# RADIO.net
KiCad netlist of a schematic drawn in Altium Designer
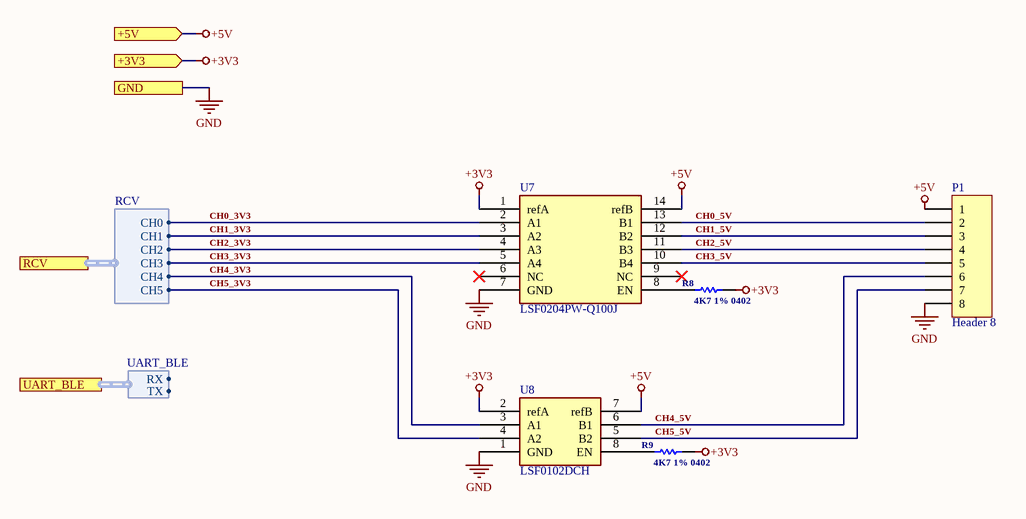
[diagram p0: RADIO.SchDoc]

(export (version "E")
  (design (tool "Eeschema 10.0.6"))
  (components
    (comp (ref "P1")
      (value "Header 8")
      (footprint "HDR1X8")
      (description "Header, 8-Pin")
      (fields (field (name "PUBLISHER") "Altium Limited"))
      (libsource (lib "Miscellaneous Connectors") (part "Header 8"))
    )
    (comp (ref "R8")
      (value "4K7 1% 0402")
      (footprint "Resistor_0402")
      (description "Thick Film Resistors 1/16W 4.7K ohm 1% AEC-Q200")
      (fields
        (field (name "MANUFACTURER") "Yageo")
        (field (name "MANUFACTURER PART NUMBER") "AC0402FR-074K7L")
      )
      (libsource (lib "ResistenciasGenericas") (part "AC0402FR-074K7L 4.7K 1% 0402"))
    )
    (comp (ref "R9")
      (value "4K7 1% 0402")
      (footprint "Resistor_0402")
      (description "Thick Film Resistors 1/16W 4.7K ohm 1% AEC-Q200")
      (fields
        (field (name "MANUFACTURER") "Yageo")
        (field (name "MANUFACTURER PART NUMBER") "AC0402FR-074K7L")
      )
      (libsource (lib "ResistenciasGenericas") (part "AC0402FR-074K7L 4.7K 1% 0402"))
    )
    (comp (ref "U7")
      (value "LSF0204PW-Q100J")
      (footprint "TSOP65P640X110-14N")
      (description "Nivel de voltaje Traductores Bidireccional 1 circuitos 4 canales 120MHz 14-TSSOP")
      (libsource (lib "LevelConversors") (part "LSF0204PW-Q100J"))
    )
    (comp (ref "U8")
      (value "LSF0102DCH")
      (description "Voltage Level Translator Bidirectional 1 Circuit 2 Channel 100MHz 8-VSSOP")
      (libsource (lib "LevelConversors") (part "LSF0102DCH"))
    )
  )
  (nets
    (net (code "3") (name "+3V3") (class "Default")
      (node (ref "R8") (pin "2") (pinfunction "2_2") (pintype "passive"))
      (node (ref "R9") (pin "2") (pinfunction "2_2") (pintype "passive"))
      (node (ref "U7") (pin "1") (pinfunction "refA_1") (pintype "passive"))
      (node (ref "U8") (pin "2") (pinfunction "refA_2") (pintype "passive"))
    )
    (net (code "4") (name "+5V") (class "Default")
      (node (ref "P1") (pin "1") (pinfunction "1_1") (pintype "passive"))
      (node (ref "U7") (pin "14") (pinfunction "refB_14") (pintype "passive"))
      (node (ref "U8") (pin "7") (pinfunction "refB_7") (pintype "passive"))
    )
    (net (code "5") (name "/CH0_3V3") (class "Default")
      (node (ref "U7") (pin "2") (pinfunction "A1_2") (pintype "passive"))
    )
    (net (code "6") (name "/CH0_5V") (class "Default")
      (node (ref "P1") (pin "2") (pinfunction "2_2") (pintype "passive"))
      (node (ref "U7") (pin "13") (pinfunction "B1_13") (pintype "passive"))
    )
    (net (code "7") (name "/CH1_3V3") (class "Default")
      (node (ref "U7") (pin "3") (pinfunction "A2_3") (pintype "passive"))
    )
    (net (code "8") (name "/CH1_5V") (class "Default")
      (node (ref "P1") (pin "3") (pinfunction "3_3") (pintype "passive"))
      (node (ref "U7") (pin "12") (pinfunction "B2_12") (pintype "passive"))
    )
    (net (code "9") (name "/CH2_3V3") (class "Default")
      (node (ref "U7") (pin "4") (pinfunction "A3_4") (pintype "passive"))
    )
    (net (code "10") (name "/CH2_5V") (class "Default")
      (node (ref "P1") (pin "4") (pinfunction "4_4") (pintype "passive"))
      (node (ref "U7") (pin "11") (pinfunction "B3_11") (pintype "passive"))
    )
    (net (code "11") (name "/CH3_3V3") (class "Default")
      (node (ref "U7") (pin "5") (pinfunction "A4_5") (pintype "passive"))
    )
    (net (code "12") (name "/CH3_5V") (class "Default")
      (node (ref "P1") (pin "5") (pinfunction "5_5") (pintype "passive"))
      (node (ref "U7") (pin "10") (pinfunction "B4_10") (pintype "passive"))
    )
    (net (code "13") (name "/CH4_3V3") (class "Default")
      (node (ref "U8") (pin "3") (pinfunction "A1_3") (pintype "passive"))
    )
    (net (code "14") (name "/CH4_5V") (class "Default")
      (node (ref "P1") (pin "6") (pinfunction "6_6") (pintype "passive"))
      (node (ref "U8") (pin "6") (pinfunction "B1_6") (pintype "passive"))
    )
    (net (code "15") (name "/CH5_3V3") (class "Default")
      (node (ref "U8") (pin "4") (pinfunction "A2_4") (pintype "passive"))
    )
    (net (code "16") (name "/CH5_5V") (class "Default")
      (node (ref "P1") (pin "7") (pinfunction "7_7") (pintype "passive"))
      (node (ref "U8") (pin "5") (pinfunction "B2_5") (pintype "passive"))
    )
    (net (code "19") (name "GND") (class "Default")
      (node (ref "P1") (pin "8") (pinfunction "8_8") (pintype "passive"))
      (node (ref "U7") (pin "7") (pinfunction "GND_7") (pintype "passive"))
      (node (ref "U8") (pin "1") (pinfunction "GND_1") (pintype "passive"))
    )
    (net (code "20") (name "Net-(U7-EN)") (class "Default")
      (node (ref "R8") (pin "1") (pinfunction "1_1") (pintype "passive"))
      (node (ref "U7") (pin "8") (pinfunction "EN_8") (pintype "passive"))
    )
    (net (code "21") (name "Net-(U8-EN)") (class "Default")
      (node (ref "R9") (pin "1") (pinfunction "1_1") (pintype "passive"))
      (node (ref "U8") (pin "8") (pinfunction "EN_8") (pintype "passive"))
    )
    (net (code "22") (name "unconnected-(U7-NC-Pad6)") (class "Default")
      (node (ref "U7") (pin "6") (pinfunction "NC_6") (pintype "passive+no_connect"))
    )
    (net (code "23") (name "unconnected-(U7-NC-Pad9)") (class "Default")
      (node (ref "U7") (pin "9") (pinfunction "NC_9") (pintype "passive+no_connect"))
    )
  )
)
